# 304_usb_serial020001.net
KiCad netlist of a schematic drawn in EAGLE
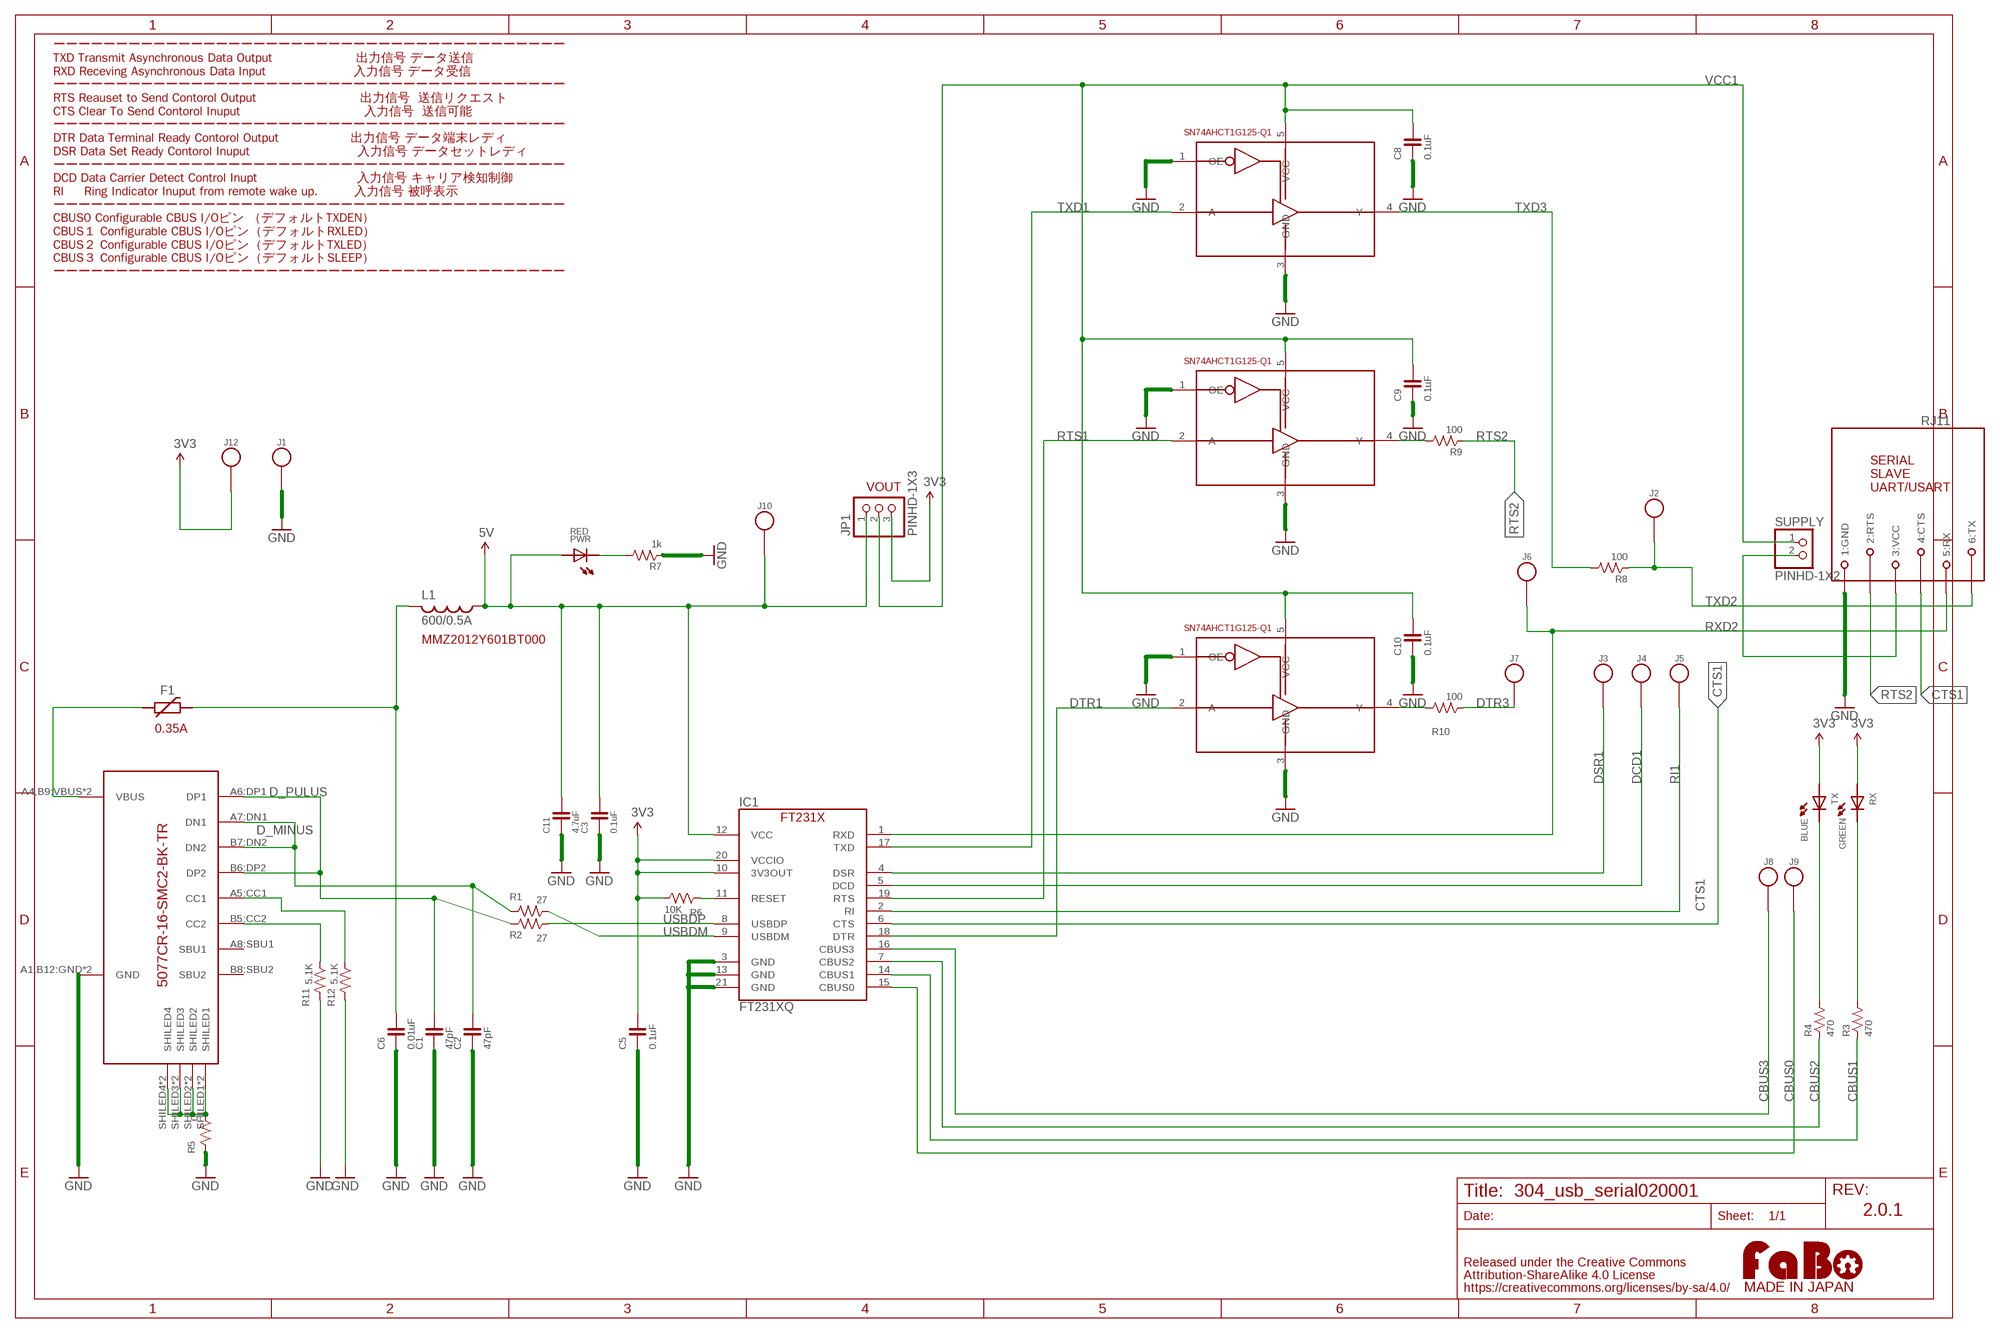
[diagram p0: schematic, sheet 1]

(export (version "E")
  (design (tool "Eeschema 10.0.6"))
  (components
    (comp (ref "C1")
      (value "47pF")
      (footprint "eagle-import:0402")
      (libsource (lib "eagle-import") (part "CAPACITOR-0402"))
    )
    (comp (ref "C2")
      (value "47pF")
      (footprint "eagle-import:0402")
      (libsource (lib "eagle-import") (part "CAPACITOR-0402"))
    )
    (comp (ref "C3")
      (value "0.1uF")
      (footprint "eagle-import:0402")
      (libsource (lib "eagle-import") (part "CAPACITOR-0402"))
    )
    (comp (ref "C5")
      (value "0.1uF")
      (footprint "eagle-import:0402")
      (libsource (lib "eagle-import") (part "CAPACITOR-0402"))
    )
    (comp (ref "C6")
      (value "0.01uF")
      (footprint "eagle-import:0402")
      (libsource (lib "eagle-import") (part "CAPACITOR-0402"))
    )
    (comp (ref "C8")
      (value "0.1uF")
      (footprint "eagle-import:0402")
      (libsource (lib "eagle-import") (part "CAPACITOR-0402"))
    )
    (comp (ref "C9")
      (value "0.1uF")
      (footprint "eagle-import:0402")
      (libsource (lib "eagle-import") (part "CAPACITOR-0402"))
    )
    (comp (ref "C10")
      (value "0.1uF")
      (footprint "eagle-import:0402")
      (libsource (lib "eagle-import") (part "CAPACITOR-0402"))
    )
    (comp (ref "C11")
      (value "4.7uF")
      (footprint "eagle-import:0402")
      (libsource (lib "eagle-import") (part "CAPACITOR-0402"))
    )
    (comp (ref "F1")
      (value "350mA")
      (footprint "eagle-import:NANOSMDC035F")
      (libsource (lib "eagle-import") (part "POLYSWITCH"))
    )
    (comp (ref "IC1")
      (value "FT231XQ")
      (footprint "eagle-import:QFN-20_FT231X")
      (libsource (lib "eagle-import") (part "FT231XQ"))
    )
    (comp (ref "J1")
      (value "PIN_HEADER_1X1_NOLABEL_C")
      (footprint "eagle-import:PIN_1X1_NOLABEL")
      (libsource (lib "eagle-import") (part "PIN_HEADER_1X1_NOLABEL_C"))
    )
    (comp (ref "J2")
      (value "PIN_HEADER_1X1_NOLABEL_C")
      (footprint "eagle-import:PIN_1X1_NOLABEL")
      (libsource (lib "eagle-import") (part "PIN_HEADER_1X1_NOLABEL_C"))
    )
    (comp (ref "J3")
      (value "PIN_HEADER_1X1_NOLABEL_C")
      (footprint "eagle-import:PIN_1X1_NOLABEL")
      (libsource (lib "eagle-import") (part "PIN_HEADER_1X1_NOLABEL_C"))
    )
    (comp (ref "J4")
      (value "PIN_HEADER_1X1_NOLABEL_C")
      (footprint "eagle-import:PIN_1X1_NOLABEL")
      (libsource (lib "eagle-import") (part "PIN_HEADER_1X1_NOLABEL_C"))
    )
    (comp (ref "J5")
      (value "PIN_HEADER_1X1_NOLABEL_C")
      (footprint "eagle-import:PIN_1X1_NOLABEL")
      (libsource (lib "eagle-import") (part "PIN_HEADER_1X1_NOLABEL_C"))
    )
    (comp (ref "J6")
      (value "PIN_HEADER_1X1_NOLABEL_C")
      (footprint "eagle-import:PIN_1X1_NOLABEL")
      (libsource (lib "eagle-import") (part "PIN_HEADER_1X1_NOLABEL_C"))
    )
    (comp (ref "J7")
      (value "PIN_HEADER_1X1_NOLABEL_C")
      (footprint "eagle-import:PIN_1X1_NOLABEL")
      (libsource (lib "eagle-import") (part "PIN_HEADER_1X1_NOLABEL_C"))
    )
    (comp (ref "J8")
      (value "PIN_HEADER_1X1_NOLABEL_C")
      (footprint "eagle-import:PIN_1X1_NOLABEL")
      (libsource (lib "eagle-import") (part "PIN_HEADER_1X1_NOLABEL_C"))
    )
    (comp (ref "J9")
      (value "PIN_HEADER_1X1_NOLABEL_C")
      (footprint "eagle-import:PIN_1X1_NOLABEL")
      (libsource (lib "eagle-import") (part "PIN_HEADER_1X1_NOLABEL_C"))
    )
    (comp (ref "J10")
      (value "PIN_HEADER_1X1_NOLABEL_C")
      (footprint "eagle-import:PIN_1X1_NOLABEL")
      (libsource (lib "eagle-import") (part "PIN_HEADER_1X1_NOLABEL_C"))
    )
    (comp (ref "J12")
      (value "PIN_HEADER_1X1_NOLABEL_C")
      (footprint "eagle-import:PIN_1X1_NOLABEL")
      (libsource (lib "eagle-import") (part "PIN_HEADER_1X1_NOLABEL_C"))
    )
    (comp (ref "JP1")
      (value "PINHD-1X3")
      (footprint "eagle-import:1X03")
      (libsource (lib "eagle-import") (part "PINHD-1X3"))
    )
    (comp (ref "L1")
      (value "600/0.5A")
      (footprint "eagle-import:RESC0805_L")
      (libsource (lib "eagle-import") (part "INDUCTOR_0805_L"))
    )
    (comp (ref "PWR")
      (value "RED")
      (footprint "eagle-import:0603-NARROW")
      (libsource (lib "eagle-import") (part "LED-0603-NARROW"))
    )
    (comp (ref "R1")
      (value "27")
      (footprint "eagle-import:0603-NARROW")
      (libsource (lib "eagle-import") (part "RESISTOR-0603-NARROW"))
    )
    (comp (ref "R2")
      (value "27")
      (footprint "eagle-import:0603-NARROW")
      (libsource (lib "eagle-import") (part "RESISTOR-0603-NARROW"))
    )
    (comp (ref "R3")
      (value "470")
      (footprint "eagle-import:0603-NARROW")
      (libsource (lib "eagle-import") (part "RESISTOR-0603-NARROW"))
    )
    (comp (ref "R4")
      (value "470")
      (footprint "eagle-import:0603-NARROW")
      (libsource (lib "eagle-import") (part "RESISTOR-0603-NARROW"))
    )
    (comp (ref "R5")
      (value "0")
      (footprint "eagle-import:0603-NARROW")
      (libsource (lib "eagle-import") (part "RESISTOR-0603-NARROW"))
    )
    (comp (ref "R6")
      (value "10K")
      (footprint "eagle-import:0603-NARROW")
      (libsource (lib "eagle-import") (part "RESISTOR-0603-NARROW"))
    )
    (comp (ref "R7")
      (value "1k")
      (footprint "eagle-import:0603-NARROW")
      (libsource (lib "eagle-import") (part "RESISTOR-0603-NARROW"))
    )
    (comp (ref "R8")
      (value "100")
      (footprint "eagle-import:0603-NARROW")
      (libsource (lib "eagle-import") (part "RESISTOR-0603-NARROW"))
    )
    (comp (ref "R9")
      (value "100")
      (footprint "eagle-import:0603-NARROW")
      (libsource (lib "eagle-import") (part "RESISTOR-0603-NARROW"))
    )
    (comp (ref "R10")
      (value "100")
      (footprint "eagle-import:0603-NARROW")
      (libsource (lib "eagle-import") (part "RESISTOR-0603-NARROW"))
    )
    (comp (ref "R11")
      (value "5.1K")
      (footprint "eagle-import:0603-NARROW")
      (libsource (lib "eagle-import") (part "RESISTOR-0603-NARROW"))
    )
    (comp (ref "R12")
      (value "5.1K")
      (footprint "eagle-import:0603-NARROW")
      (libsource (lib "eagle-import") (part "RESISTOR-0603-NARROW"))
    )
    (comp (ref "RJ11")
      (value "MODULAR-JACK-6P-RJ11_SERIAL_S_USART")
      (footprint "eagle-import:7002-6PXC-X")
      (libsource (lib "eagle-import") (part "MODULAR-JACK-6P-RJ11_SERIAL_S_USART"))
    )
    (comp (ref "RX")
      (value "GREEN")
      (footprint "eagle-import:0603-NARROW")
      (libsource (lib "eagle-import") (part "LED-0603-NARROW"))
    )
    (comp (ref "SUPPLY")
      (value "PINHD-1X2")
      (footprint "eagle-import:1X02")
      (libsource (lib "eagle-import") (part "PINHD-1X2"))
    )
    (comp (ref "TX")
      (value "BLUE")
      (footprint "eagle-import:0603-NARROW")
      (libsource (lib "eagle-import") (part "LED-0603-NARROW"))
    )
    (comp (ref "U$2")
      (value "LOGO_FABO-M_BOTTOM")
      (footprint "eagle-import:LOGO_FABO_MS_BOTTOM")
      (libsource (lib "eagle-import") (part "LOGO_FABO-M_BOTTOM"))
    )
    (comp (ref "U$4")
      (value "5077CR-16-SMC2-BK-TR")
      (footprint "eagle-import:5077CR-16-SMC2-BK-TR")
      (libsource (lib "eagle-import") (part "5077CR-16-SMC2-BK-TR"))
    )
    (comp (ref "U$6")
      (value "SN74AHCT1G125-Q1")
      (footprint "eagle-import:SC70")
      (libsource (lib "eagle-import") (part "SN74AHCT1G125-Q1"))
    )
    (comp (ref "U$7")
      (value "SN74AHCT1G125-Q1")
      (footprint "eagle-import:SC70")
      (libsource (lib "eagle-import") (part "SN74AHCT1G125-Q1"))
    )
    (comp (ref "U$8")
      (value "SN74AHCT1G125-Q1")
      (footprint "eagle-import:SC70")
      (libsource (lib "eagle-import") (part "SN74AHCT1G125-Q1"))
    )
  )
  (nets
    (net (code "1") (name "/CBUS0") (class "Default")
      (node (ref "IC1") (pin "15") (pinfunction "CBUS0_15") (pintype "bidirectional"))
      (node (ref "J9") (pin "1") (pinfunction "1_1") (pintype "bidirectional"))
    )
    (net (code "2") (name "/CBUS1") (class "Default")
      (node (ref "IC1") (pin "14") (pinfunction "CBUS1_14") (pintype "bidirectional"))
      (node (ref "R3") (pin "1") (pinfunction "1_1") (pintype "bidirectional"))
    )
    (net (code "3") (name "/CBUS2") (class "Default")
      (node (ref "IC1") (pin "7") (pinfunction "CBUS2_7") (pintype "bidirectional"))
      (node (ref "R4") (pin "1") (pinfunction "1_1") (pintype "bidirectional"))
    )
    (net (code "4") (name "/CBUS3") (class "Default")
      (node (ref "IC1") (pin "16") (pinfunction "CBUS3_16") (pintype "bidirectional"))
      (node (ref "J8") (pin "1") (pinfunction "1_1") (pintype "bidirectional"))
    )
    (net (code "5") (name "/DCD1") (class "Default")
      (node (ref "IC1") (pin "5") (pinfunction "DCD_5") (pintype "bidirectional"))
      (node (ref "J4") (pin "1") (pinfunction "1_1") (pintype "bidirectional"))
    )
    (net (code "6") (name "/DSR1") (class "Default")
      (node (ref "IC1") (pin "4") (pinfunction "DSR_4") (pintype "bidirectional"))
      (node (ref "J3") (pin "1") (pinfunction "1_1") (pintype "bidirectional"))
    )
    (net (code "7") (name "/DTR1") (class "Default")
      (node (ref "IC1") (pin "18") (pinfunction "DTR_18") (pintype "bidirectional"))
      (node (ref "U$8") (pin "2") (pinfunction "A_2") (pintype "bidirectional"))
    )
    (net (code "8") (name "/DTR3") (class "Default")
      (node (ref "J7") (pin "1") (pinfunction "1_1") (pintype "bidirectional"))
      (node (ref "R10") (pin "1") (pinfunction "1_1") (pintype "bidirectional"))
    )
    (net (code "9") (name "/D_MINUS") (class "Default")
      (node (ref "C2") (pin "2") (pinfunction "2_2") (pintype "passive"))
      (node (ref "R1") (pin "2") (pinfunction "2_2") (pintype "bidirectional"))
      (node (ref "U$4") (pin "A7:DN1") (pinfunction "DN1_A7:DN1") (pintype "bidirectional"))
      (node (ref "U$4") (pin "B7:DN2") (pinfunction "DN2_B7:DN2") (pintype "bidirectional"))
    )
    (net (code "10") (name "/D_PULUS") (class "Default")
      (node (ref "C1") (pin "2") (pinfunction "2_2") (pintype "passive"))
      (node (ref "R2") (pin "2") (pinfunction "2_2") (pintype "bidirectional"))
      (node (ref "U$4") (pin "A6:DP1") (pinfunction "DP1_A6:DP1") (pintype "bidirectional"))
      (node (ref "U$4") (pin "B6:DP2") (pinfunction "DP2_B6:DP2") (pintype "bidirectional"))
    )
    (net (code "11") (name "/RI1") (class "Default")
      (node (ref "IC1") (pin "2") (pinfunction "RI_2") (pintype "bidirectional"))
      (node (ref "J5") (pin "1") (pinfunction "1_1") (pintype "bidirectional"))
    )
    (net (code "12") (name "/RTS1") (class "Default")
      (node (ref "IC1") (pin "19") (pinfunction "RTS_19") (pintype "bidirectional"))
      (node (ref "U$7") (pin "2") (pinfunction "A_2") (pintype "bidirectional"))
    )
    (net (code "13") (name "/RXD2") (class "Default")
      (node (ref "IC1") (pin "1") (pinfunction "RXD_1") (pintype "bidirectional"))
      (node (ref "J6") (pin "1") (pinfunction "1_1") (pintype "bidirectional"))
      (node (ref "RJ11") (pin "5") (pinfunction "5:RX_5") (pintype "output"))
    )
    (net (code "14") (name "/TXD1") (class "Default")
      (node (ref "IC1") (pin "17") (pinfunction "TXD_17") (pintype "bidirectional"))
      (node (ref "U$6") (pin "2") (pinfunction "A_2") (pintype "bidirectional"))
    )
    (net (code "15") (name "/TXD2") (class "Default")
      (node (ref "J2") (pin "1") (pinfunction "1_1") (pintype "bidirectional"))
      (node (ref "R8") (pin "1") (pinfunction "1_1") (pintype "bidirectional"))
      (node (ref "RJ11") (pin "6") (pinfunction "6:TX_6") (pintype "input"))
    )
    (net (code "16") (name "/TXD3") (class "Default")
      (node (ref "R8") (pin "2") (pinfunction "2_2") (pintype "bidirectional"))
      (node (ref "U$6") (pin "4") (pinfunction "Y_4") (pintype "bidirectional"))
    )
    (net (code "17") (name "/USBDM") (class "Default")
      (node (ref "IC1") (pin "9") (pinfunction "USBDM_9") (pintype "bidirectional"))
      (node (ref "R1") (pin "1") (pinfunction "1_1") (pintype "bidirectional"))
    )
    (net (code "18") (name "/USBDP") (class "Default")
      (node (ref "IC1") (pin "8") (pinfunction "USBDP_8") (pintype "bidirectional"))
      (node (ref "R2") (pin "1") (pinfunction "1_1") (pintype "bidirectional"))
    )
    (net (code "19") (name "/VCC1") (class "Default")
      (node (ref "C10") (pin "2") (pinfunction "2_2") (pintype "passive"))
      (node (ref "C8") (pin "2") (pinfunction "2_2") (pintype "passive"))
      (node (ref "C9") (pin "2") (pinfunction "2_2") (pintype "passive"))
      (node (ref "JP1") (pin "2") (pinfunction "2_2") (pintype "passive"))
      (node (ref "SUPPLY") (pin "1") (pinfunction "1_1") (pintype "passive"))
      (node (ref "U$6") (pin "5") (pinfunction "VCC_5") (pintype "bidirectional"))
      (node (ref "U$7") (pin "5") (pinfunction "VCC_5") (pintype "bidirectional"))
      (node (ref "U$8") (pin "5") (pinfunction "VCC_5") (pintype "bidirectional"))
    )
    (net (code "20") (name "3V3") (class "Default")
      (node (ref "C5") (pin "2") (pinfunction "2_2") (pintype "passive"))
      (node (ref "IC1") (pin "10") (pinfunction "3V3OUT_10") (pintype "bidirectional"))
      (node (ref "IC1") (pin "20") (pinfunction "VCCIO_20") (pintype "bidirectional"))
      (node (ref "J12") (pin "1") (pinfunction "1_1") (pintype "bidirectional"))
      (node (ref "JP1") (pin "3") (pinfunction "3_3") (pintype "passive"))
      (node (ref "R6") (pin "1") (pinfunction "1_1") (pintype "bidirectional"))
      (node (ref "RX") (pin "ANODE") (pinfunction "ANODE_ANODE") (pintype "passive"))
      (node (ref "TX") (pin "ANODE") (pinfunction "ANODE_ANODE") (pintype "passive"))
    )
    (net (code "21") (name "5V") (class "Default")
      (node (ref "C11") (pin "2") (pinfunction "2_2") (pintype "passive"))
      (node (ref "C3") (pin "2") (pinfunction "2_2") (pintype "passive"))
      (node (ref "IC1") (pin "12") (pinfunction "VCC_12") (pintype "bidirectional"))
      (node (ref "J10") (pin "1") (pinfunction "1_1") (pintype "bidirectional"))
      (node (ref "JP1") (pin "1") (pinfunction "1_1") (pintype "passive"))
      (node (ref "L1") (pin "1") (pinfunction "1_1") (pintype "passive"))
      (node (ref "PWR") (pin "ANODE") (pinfunction "ANODE_ANODE") (pintype "passive"))
    )
    (net (code "22") (name "CTS1") (class "Default")
      (node (ref "IC1") (pin "6") (pinfunction "CTS_6") (pintype "bidirectional"))
      (node (ref "RJ11") (pin "4") (pinfunction "4:CTS_4") (pintype "bidirectional"))
    )
    (net (code "23") (name "GND") (class "Default")
      (node (ref "C1") (pin "1") (pinfunction "1_1") (pintype "passive"))
      (node (ref "C10") (pin "1") (pinfunction "1_1") (pintype "passive"))
      (node (ref "C11") (pin "1") (pinfunction "1_1") (pintype "passive"))
      (node (ref "C2") (pin "1") (pinfunction "1_1") (pintype "passive"))
      (node (ref "C3") (pin "1") (pinfunction "1_1") (pintype "passive"))
      (node (ref "C5") (pin "1") (pinfunction "1_1") (pintype "passive"))
      (node (ref "C6") (pin "1") (pinfunction "1_1") (pintype "passive"))
      (node (ref "C8") (pin "1") (pinfunction "1_1") (pintype "passive"))
      (node (ref "C9") (pin "1") (pinfunction "1_1") (pintype "passive"))
      (node (ref "IC1") (pin "13") (pinfunction "GND_13") (pintype "bidirectional"))
      (node (ref "IC1") (pin "21") (pinfunction "GND_21") (pintype "bidirectional"))
      (node (ref "IC1") (pin "3") (pinfunction "GND_3") (pintype "bidirectional"))
      (node (ref "J1") (pin "1") (pinfunction "1_1") (pintype "bidirectional"))
      (node (ref "R11") (pin "2") (pinfunction "2_2") (pintype "bidirectional"))
      (node (ref "R12") (pin "2") (pinfunction "2_2") (pintype "bidirectional"))
      (node (ref "R5") (pin "2") (pinfunction "2_2") (pintype "bidirectional"))
      (node (ref "R7") (pin "1") (pinfunction "1_1") (pintype "bidirectional"))
      (node (ref "RJ11") (pin "1") (pinfunction "1:GND_1") (pintype "power_in"))
      (node (ref "U$4") (pin "A1,B12:GND") (pinfunction "GND_A1,B12:GND") (pintype "power_in"))
      (node (ref "U$4") (pin "B1,A12:GND") (pinfunction "GND_B1,A12:GND") (pintype "power_in"))
      (node (ref "U$6") (pin "1") (pinfunction "OE_1") (pintype "bidirectional"))
      (node (ref "U$6") (pin "3") (pinfunction "GND_3") (pintype "bidirectional"))
      (node (ref "U$7") (pin "1") (pinfunction "OE_1") (pintype "bidirectional"))
      (node (ref "U$7") (pin "3") (pinfunction "GND_3") (pintype "bidirectional"))
      (node (ref "U$8") (pin "1") (pinfunction "OE_1") (pintype "bidirectional"))
      (node (ref "U$8") (pin "3") (pinfunction "GND_3") (pintype "bidirectional"))
    )
    (net (code "24") (name "Net-(C6-Pad2)") (class "Default")
      (node (ref "C6") (pin "2") (pinfunction "2_2") (pintype "passive"))
      (node (ref "F1") (pin "2") (pinfunction "2_2") (pintype "bidirectional"))
      (node (ref "L1") (pin "2") (pinfunction "2_2") (pintype "passive"))
    )
    (net (code "25") (name "Net-(F1-Pad1)") (class "Default")
      (node (ref "F1") (pin "1") (pinfunction "1_1") (pintype "bidirectional"))
      (node (ref "U$4") (pin "A4,B9:VBUS") (pinfunction "VBUS_A4,B9:VBUS") (pintype "power_in"))
      (node (ref "U$4") (pin "B4,A9:VBUS") (pinfunction "VBUS_B4,A9:VBUS") (pintype "power_in"))
    )
    (net (code "26") (name "Net-(IC1-RESET)") (class "Default")
      (node (ref "IC1") (pin "11") (pinfunction "RESET_11") (pintype "bidirectional"))
      (node (ref "R6") (pin "2") (pinfunction "2_2") (pintype "bidirectional"))
    )
    (net (code "27") (name "Net-(PWR-PadCATHODE)") (class "Default")
      (node (ref "PWR") (pin "CATHODE") (pinfunction "CATHODE_CATHODE") (pintype "passive"))
      (node (ref "R7") (pin "2") (pinfunction "2_2") (pintype "bidirectional"))
    )
    (net (code "28") (name "Net-(R3-Pad2)") (class "Default")
      (node (ref "R3") (pin "2") (pinfunction "2_2") (pintype "bidirectional"))
      (node (ref "RX") (pin "CATHODE") (pinfunction "CATHODE_CATHODE") (pintype "passive"))
    )
    (net (code "29") (name "Net-(R4-Pad2)") (class "Default")
      (node (ref "R4") (pin "2") (pinfunction "2_2") (pintype "bidirectional"))
      (node (ref "TX") (pin "CATHODE") (pinfunction "CATHODE_CATHODE") (pintype "passive"))
    )
    (net (code "30") (name "Net-(R5-Pad1)") (class "Default")
      (node (ref "R5") (pin "1") (pinfunction "1_1") (pintype "bidirectional"))
      (node (ref "U$4") (pin "SHILED1") (pinfunction "SHILED1_SHILED1") (pintype "bidirectional"))
      (node (ref "U$4") (pin "SHILED2") (pinfunction "SHILED2_SHILED2") (pintype "bidirectional"))
      (node (ref "U$4") (pin "SHILED3") (pinfunction "SHILED3_SHILED3") (pintype "bidirectional"))
      (node (ref "U$4") (pin "SHILED4") (pinfunction "SHILED4_SHILED4") (pintype "bidirectional"))
      (node (ref "U$4") (pin "SHILED5") (pinfunction "SHILED1_SHILED5") (pintype "bidirectional"))
      (node (ref "U$4") (pin "SHILED6") (pinfunction "SHILED2_SHILED6") (pintype "bidirectional"))
      (node (ref "U$4") (pin "SHILED7") (pinfunction "SHILED3_SHILED7") (pintype "bidirectional"))
      (node (ref "U$4") (pin "SHILED8") (pinfunction "SHILED4_SHILED8") (pintype "bidirectional"))
    )
    (net (code "31") (name "Net-(RJ11-3:VCC)") (class "Default")
      (node (ref "RJ11") (pin "3") (pinfunction "3:VCC_3") (pintype "power_in"))
      (node (ref "SUPPLY") (pin "2") (pinfunction "2_2") (pintype "passive"))
    )
    (net (code "32") (name "Net-(U$4-CC1)") (class "Default")
      (node (ref "R12") (pin "1") (pinfunction "1_1") (pintype "bidirectional"))
      (node (ref "U$4") (pin "A5:CC1") (pinfunction "CC1_A5:CC1") (pintype "bidirectional"))
    )
    (net (code "33") (name "Net-(U$4-CC2)") (class "Default")
      (node (ref "R11") (pin "1") (pinfunction "1_1") (pintype "bidirectional"))
      (node (ref "U$4") (pin "B5:CC2") (pinfunction "CC2_B5:CC2") (pintype "bidirectional"))
    )
    (net (code "34") (name "Net-(U$7-Y)") (class "Default")
      (node (ref "R9") (pin "2") (pinfunction "2_2") (pintype "bidirectional"))
      (node (ref "U$7") (pin "4") (pinfunction "Y_4") (pintype "bidirectional"))
    )
    (net (code "35") (name "Net-(U$8-Y)") (class "Default")
      (node (ref "R10") (pin "2") (pinfunction "2_2") (pintype "bidirectional"))
      (node (ref "U$8") (pin "4") (pinfunction "Y_4") (pintype "bidirectional"))
    )
    (net (code "36") (name "RTS2") (class "Default")
      (node (ref "R9") (pin "1") (pinfunction "1_1") (pintype "bidirectional"))
      (node (ref "RJ11") (pin "2") (pinfunction "2:RTS_2") (pintype "bidirectional"))
    )
    (net (code "37") (name "unconnected-(U$4-SBU1-PadA8:SBU1)") (class "Default")
      (node (ref "U$4") (pin "A8:SBU1") (pinfunction "SBU1_A8:SBU1") (pintype "bidirectional"))
    )
    (net (code "38") (name "unconnected-(U$4-SBU2-PadB8:SBU2)") (class "Default")
      (node (ref "U$4") (pin "B8:SBU2") (pinfunction "SBU2_B8:SBU2") (pintype "bidirectional"))
    )
  )
)
